# Ribatski_EPS-v2_0.net
KiCad netlist of a schematic drawn in EAGLE
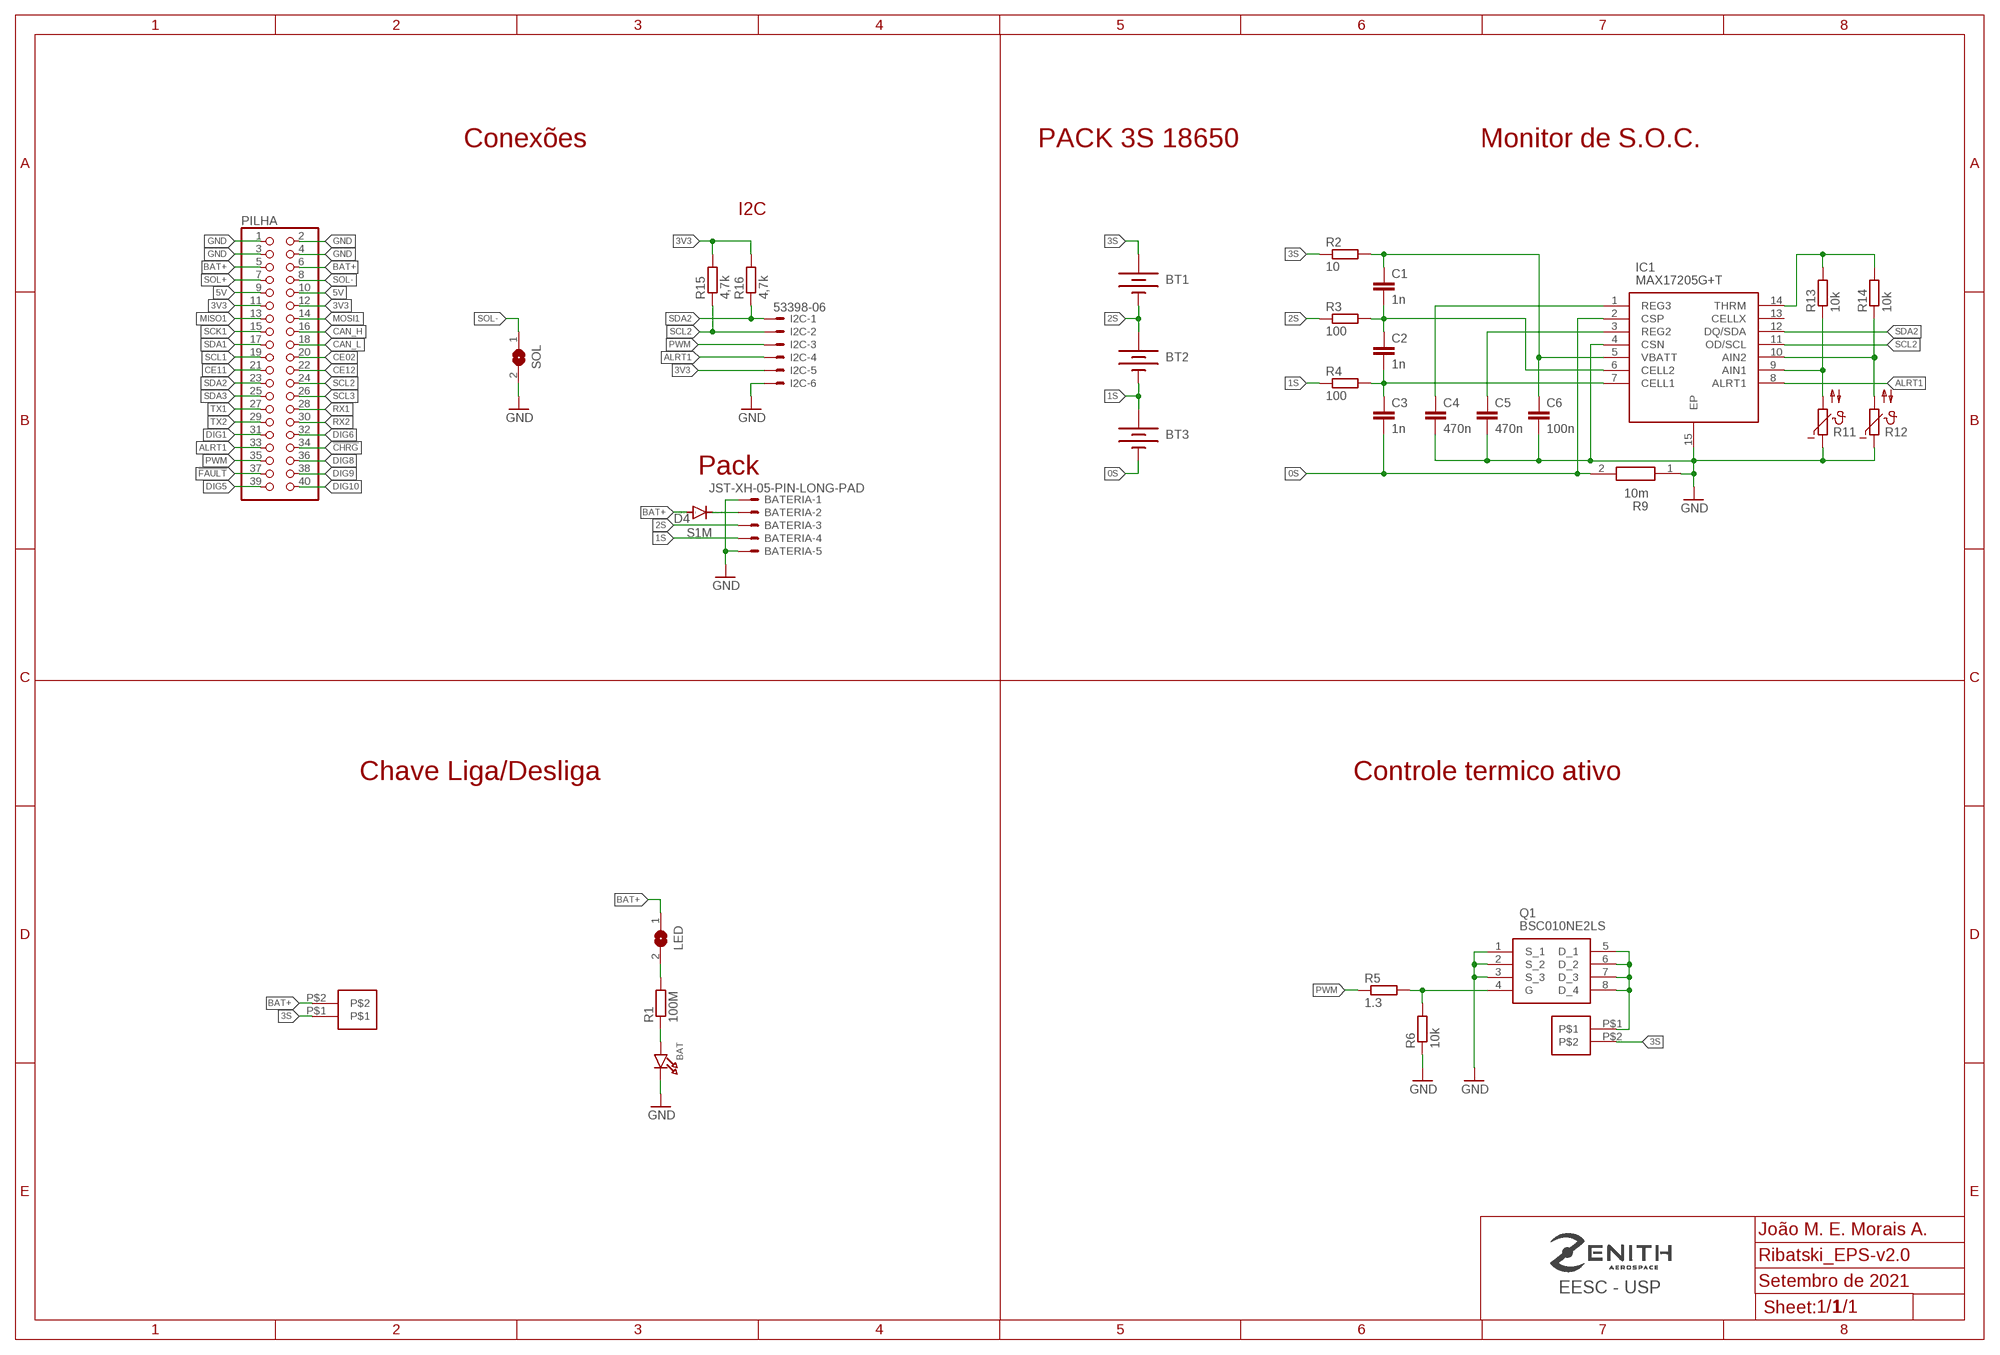
[diagram p0: schematic, sheet 1]

(export (version "E")
  (design (tool "Eeschema 10.0.6"))
  (components
    (comp (ref "BAT")
      (value "LED1206")
      (footprint "eagle-import:CHIPLED_1206")
      (libsource (lib "eagle-import") (part "LED1206"))
    )
    (comp (ref "BATERIA")
      (value "JST-XH-05-PIN-LONG-PAD")
      (footprint "eagle-import:JST-XH-05-PACKAGE-LONG-PAD")
      (libsource (lib "eagle-import") (part "JST-XH-05-PIN-LONG-PAD"))
    )
    (comp (ref "BT1")
      (value "BATTERY-18650")
      (footprint "eagle-import:BATTERY_18650-HOLDER")
      (libsource (lib "eagle-import") (part "BATTERY-18650"))
    )
    (comp (ref "BT2")
      (value "BATTERY-18650")
      (footprint "eagle-import:BATTERY_18650-HOLDER")
      (libsource (lib "eagle-import") (part "BATTERY-18650"))
    )
    (comp (ref "BT3")
      (value "BATTERY-18650")
      (footprint "eagle-import:BATTERY_18650-HOLDER")
      (libsource (lib "eagle-import") (part "BATTERY-18650"))
    )
    (comp (ref "C1")
      (value "1n")
      (footprint "eagle-import:C0805")
      (libsource (lib "eagle-import") (part "C-EUC0805"))
    )
    (comp (ref "C2")
      (value "1n")
      (footprint "eagle-import:C0805")
      (libsource (lib "eagle-import") (part "C-EUC0805"))
    )
    (comp (ref "C3")
      (value "1n")
      (footprint "eagle-import:C0805")
      (libsource (lib "eagle-import") (part "C-EUC0805"))
    )
    (comp (ref "C4")
      (value "470n")
      (footprint "eagle-import:C0805")
      (libsource (lib "eagle-import") (part "C-EUC0805"))
    )
    (comp (ref "C5")
      (value "470n")
      (footprint "eagle-import:C0805")
      (libsource (lib "eagle-import") (part "C-EUC0805"))
    )
    (comp (ref "C6")
      (value "100n")
      (footprint "eagle-import:C0805")
      (libsource (lib "eagle-import") (part "C-EUC0805"))
    )
    (comp (ref "D4")
      (value "S1M")
      (footprint "eagle-import:SMA")
      (libsource (lib "eagle-import") (part "S1M"))
    )
    (comp (ref "I2C")
      (value "53398-06")
      (footprint "eagle-import:53398-06")
      (fields (field (name "MF") "MOLEX"))
      (libsource (lib "eagle-import") (part "53?-06398"))
    )
    (comp (ref "IC1")
      (value "MAX17205G+T")
      (footprint "eagle-import:SON40P300X300X80-15N")
      (fields (field (name "MOUSER_PART_NUMBER") "700-MAX17205G+T"))
      (libsource (lib "eagle-import") (part "MAX17205G+T"))
    )
    (comp (ref "LED")
      (value "SOLDERJUMPERREFLOW_NOPASTE")
      (footprint "eagle-import:SOLDERJUMPER_REFLOW_NOPASTE")
      (libsource (lib "eagle-import") (part "SOLDERJUMPERREFLOW_NOPASTE"))
    )
    (comp (ref "PILHA")
      (value "PINHD-2X20")
      (footprint "eagle-import:2X20")
      (libsource (lib "eagle-import") (part "PINHD-2X20"))
    )
    (comp (ref "Q1")
      (value "BSC010NE2LS")
      (footprint "eagle-import:PG-TDSON-8")
      (fields (field (name "MOUSER_PART_NUMBER") "726-BSC010NE2LS"))
      (libsource (lib "eagle-import") (part "BSC010NE2LS"))
    )
    (comp (ref "R1")
      (value "100M")
      (footprint "eagle-import:R0805")
      (libsource (lib "eagle-import") (part "R-EU_R0805"))
    )
    (comp (ref "R2")
      (value "10")
      (footprint "eagle-import:0204_7")
      (libsource (lib "eagle-import") (part "R-EU_0204/7"))
    )
    (comp (ref "R3")
      (value "100")
      (footprint "eagle-import:0204_7")
      (libsource (lib "eagle-import") (part "R-EU_0204/7"))
    )
    (comp (ref "R4")
      (value "100")
      (footprint "eagle-import:0204_7")
      (libsource (lib "eagle-import") (part "R-EU_0204/7"))
    )
    (comp (ref "R5")
      (value "1.3")
      (footprint "eagle-import:R0805")
      (libsource (lib "eagle-import") (part "R-EU_R0805"))
    )
    (comp (ref "R6")
      (value "10k")
      (footprint "eagle-import:R0805")
      (libsource (lib "eagle-import") (part "R-EU_R0805"))
    )
    (comp (ref "R9")
      (value "10m")
      (footprint "eagle-import:GMR320HJBFA10L0")
      (fields
        (field (name "MANUFACTURER_PART_NUMBER") "GMR320HJBFA10L0")
        (field (name "MOUSER_PART_NUMBER") "755-GMR320HJBFA10L0")
      )
      (libsource (lib "eagle-import") (part "GMR320HJBFA10L0"))
    )
    (comp (ref "R11")
      (value "NTC640")
      (footprint "eagle-import:P640")
      (libsource (lib "eagle-import") (part "NTC640"))
    )
    (comp (ref "R12")
      (value "NTC640")
      (footprint "eagle-import:P640")
      (libsource (lib "eagle-import") (part "NTC640"))
    )
    (comp (ref "R13")
      (value "10k")
      (footprint "eagle-import:R0805")
      (libsource (lib "eagle-import") (part "R-EU_R0805"))
    )
    (comp (ref "R14")
      (value "10k")
      (footprint "eagle-import:R0805")
      (libsource (lib "eagle-import") (part "R-EU_R0805"))
    )
    (comp (ref "R15")
      (value "4,7k")
      (footprint "eagle-import:R0805")
      (libsource (lib "eagle-import") (part "R-EU_R0805"))
    )
    (comp (ref "R16")
      (value "4,7k")
      (footprint "eagle-import:R0805")
      (libsource (lib "eagle-import") (part "R-EU_R0805"))
    )
    (comp (ref "SOL")
      (value "SOLDERJUMPERREFLOW_NOPASTE")
      (footprint "eagle-import:SOLDERJUMPER_REFLOW_NOPASTE")
      (libsource (lib "eagle-import") (part "SOLDERJUMPERREFLOW_NOPASTE"))
    )
    (comp (ref "U$1")
      (value "S02B-XASS-1")
      (footprint "eagle-import:S02B-XASS-1")
      (libsource (lib "eagle-import") (part "S02B-XASS-1"))
    )
    (comp (ref "U$2")
      (value "B02B-XASK-1")
      (footprint "eagle-import:B02B-XASK-1")
      (libsource (lib "eagle-import") (part "B02B-XASK-1"))
    )
  )
  (nets
    (net (code "1") (name "/~{CHRG}") (class "Default")
      (node (ref "PILHA") (pin "34") (pinfunction "34_34") (pintype "passive"))
    )
    (net (code "2") (name "/~{FAULT}") (class "Default")
      (node (ref "PILHA") (pin "37") (pinfunction "37_37") (pintype "passive"))
    )
    (net (code "3") (name "0S") (class "Default")
      (node (ref "BT3") (pin "GND@1") (pinfunction "-_GND@1") (pintype "power_in"))
      (node (ref "C3") (pin "2") (pinfunction "2_2") (pintype "passive"))
      (node (ref "IC1") (pin "2") (pinfunction "CSP_2") (pintype "bidirectional"))
      (node (ref "R9") (pin "2") (pinfunction "2_2") (pintype "bidirectional"))
    )
    (net (code "4") (name "1S") (class "Default")
      (node (ref "BATERIA") (pin "4") (pinfunction "S_4") (pintype "passive"))
      (node (ref "BT2") (pin "GND@1") (pinfunction "-_GND@1") (pintype "power_in"))
      (node (ref "BT3") (pin "PWR@1") (pinfunction "+_PWR@1") (pintype "power_in"))
      (node (ref "R4") (pin "1") (pinfunction "1_1") (pintype "passive"))
    )
    (net (code "5") (name "2S") (class "Default")
      (node (ref "BATERIA") (pin "3") (pinfunction "S_3") (pintype "passive"))
      (node (ref "BT1") (pin "GND@1") (pinfunction "-_GND@1") (pintype "power_in"))
      (node (ref "BT2") (pin "PWR@1") (pinfunction "+_PWR@1") (pintype "power_in"))
      (node (ref "R3") (pin "1") (pinfunction "1_1") (pintype "passive"))
    )
    (net (code "6") (name "3S") (class "Default")
      (node (ref "BT1") (pin "PWR@1") (pinfunction "+_PWR@1") (pintype "power_in"))
      (node (ref "R2") (pin "1") (pinfunction "1_1") (pintype "passive"))
      (node (ref "U$1") (pin "P$1") (pinfunction "P$1_P$1") (pintype "bidirectional"))
      (node (ref "U$2") (pin "P$2") (pinfunction "P$2_P$2") (pintype "bidirectional"))
    )
    (net (code "7") (name "3V3") (class "Default")
      (node (ref "I2C") (pin "5") (pinfunction "S_5") (pintype "passive"))
      (node (ref "PILHA") (pin "11") (pinfunction "11_11") (pintype "passive"))
      (node (ref "PILHA") (pin "12") (pinfunction "12_12") (pintype "passive"))
      (node (ref "R15") (pin "2") (pinfunction "2_2") (pintype "passive"))
      (node (ref "R16") (pin "2") (pinfunction "2_2") (pintype "passive"))
    )
    (net (code "8") (name "5V") (class "Default")
      (node (ref "PILHA") (pin "10") (pinfunction "10_10") (pintype "passive"))
      (node (ref "PILHA") (pin "9") (pinfunction "9_9") (pintype "passive"))
    )
    (net (code "9") (name "ALRT1") (class "Default")
      (node (ref "I2C") (pin "4") (pinfunction "S_4") (pintype "passive"))
      (node (ref "IC1") (pin "8") (pinfunction "ALRT1_8") (pintype "bidirectional"))
      (node (ref "PILHA") (pin "33") (pinfunction "33_33") (pintype "passive"))
    )
    (net (code "10") (name "BAT+") (class "Default")
      (node (ref "D4") (pin "A") (pinfunction "A_A") (pintype "passive"))
      (node (ref "LED") (pin "1") (pinfunction "1_1") (pintype "passive"))
      (node (ref "PILHA") (pin "5") (pinfunction "5_5") (pintype "passive"))
      (node (ref "PILHA") (pin "6") (pinfunction "6_6") (pintype "passive"))
      (node (ref "U$1") (pin "P$2") (pinfunction "P$2_P$2") (pintype "bidirectional"))
    )
    (net (code "11") (name "CAN_H") (class "Default")
      (node (ref "PILHA") (pin "16") (pinfunction "16_16") (pintype "passive"))
    )
    (net (code "12") (name "CAN_L") (class "Default")
      (node (ref "PILHA") (pin "18") (pinfunction "18_18") (pintype "passive"))
    )
    (net (code "13") (name "CE02") (class "Default")
      (node (ref "PILHA") (pin "20") (pinfunction "20_20") (pintype "passive"))
    )
    (net (code "14") (name "CE11") (class "Default")
      (node (ref "PILHA") (pin "21") (pinfunction "21_21") (pintype "passive"))
    )
    (net (code "15") (name "CE12") (class "Default")
      (node (ref "PILHA") (pin "22") (pinfunction "22_22") (pintype "passive"))
    )
    (net (code "16") (name "DIG1") (class "Default")
      (node (ref "PILHA") (pin "31") (pinfunction "31_31") (pintype "passive"))
    )
    (net (code "17") (name "DIG5") (class "Default")
      (node (ref "PILHA") (pin "39") (pinfunction "39_39") (pintype "passive"))
    )
    (net (code "18") (name "DIG6") (class "Default")
      (node (ref "PILHA") (pin "32") (pinfunction "32_32") (pintype "passive"))
    )
    (net (code "19") (name "DIG8") (class "Default")
      (node (ref "PILHA") (pin "36") (pinfunction "36_36") (pintype "passive"))
    )
    (net (code "20") (name "DIG9") (class "Default")
      (node (ref "PILHA") (pin "38") (pinfunction "38_38") (pintype "passive"))
    )
    (net (code "21") (name "DIG10") (class "Default")
      (node (ref "PILHA") (pin "40") (pinfunction "40_40") (pintype "passive"))
    )
    (net (code "22") (name "GND") (class "Default")
      (node (ref "BAT") (pin "C") (pinfunction "C_C") (pintype "passive"))
      (node (ref "BATERIA") (pin "1") (pinfunction "S_1") (pintype "passive"))
      (node (ref "BATERIA") (pin "5") (pinfunction "S_5") (pintype "passive"))
      (node (ref "C4") (pin "2") (pinfunction "2_2") (pintype "passive"))
      (node (ref "C5") (pin "2") (pinfunction "2_2") (pintype "passive"))
      (node (ref "C6") (pin "2") (pinfunction "2_2") (pintype "passive"))
      (node (ref "I2C") (pin "6") (pinfunction "S_6") (pintype "passive"))
      (node (ref "IC1") (pin "15") (pinfunction "EP_15") (pintype "bidirectional"))
      (node (ref "IC1") (pin "4") (pinfunction "CSN_4") (pintype "bidirectional"))
      (node (ref "PILHA") (pin "1") (pinfunction "1_1") (pintype "passive"))
      (node (ref "PILHA") (pin "2") (pinfunction "2_2") (pintype "passive"))
      (node (ref "PILHA") (pin "3") (pinfunction "3_3") (pintype "passive"))
      (node (ref "PILHA") (pin "4") (pinfunction "4_4") (pintype "passive"))
      (node (ref "Q1") (pin "1") (pinfunction "S_1_1") (pintype "bidirectional"))
      (node (ref "Q1") (pin "2") (pinfunction "S_2_2") (pintype "bidirectional"))
      (node (ref "Q1") (pin "3") (pinfunction "S_3_3") (pintype "bidirectional"))
      (node (ref "R11") (pin "1") (pinfunction "1_1") (pintype "passive"))
      (node (ref "R12") (pin "1") (pinfunction "1_1") (pintype "passive"))
      (node (ref "R6") (pin "1") (pinfunction "1_1") (pintype "passive"))
      (node (ref "R9") (pin "1") (pinfunction "1_1") (pintype "bidirectional"))
      (node (ref "SOL") (pin "2") (pinfunction "2_2") (pintype "passive"))
    )
    (net (code "23") (name "MISO1") (class "Default")
      (node (ref "PILHA") (pin "13") (pinfunction "13_13") (pintype "passive"))
    )
    (net (code "24") (name "MOSI1") (class "Default")
      (node (ref "PILHA") (pin "14") (pinfunction "14_14") (pintype "passive"))
    )
    (net (code "25") (name "Net-(BAT-PadA)") (class "Default")
      (node (ref "BAT") (pin "A") (pinfunction "A_A") (pintype "passive"))
      (node (ref "R1") (pin "1") (pinfunction "1_1") (pintype "passive"))
    )
    (net (code "26") (name "Net-(BATERIAB-S)") (class "Default")
      (node (ref "BATERIA") (pin "2") (pinfunction "S_2") (pintype "passive"))
      (node (ref "D4") (pin "C") (pinfunction "C_C") (pintype "passive"))
    )
    (net (code "27") (name "Net-(IC1-AIN1)") (class "Default")
      (node (ref "IC1") (pin "9") (pinfunction "AIN1_9") (pintype "bidirectional"))
      (node (ref "R11") (pin "2") (pinfunction "2_2") (pintype "passive"))
      (node (ref "R13") (pin "1") (pinfunction "1_1") (pintype "passive"))
    )
    (net (code "28") (name "Net-(IC1-AIN2)") (class "Default")
      (node (ref "IC1") (pin "10") (pinfunction "AIN2_10") (pintype "bidirectional"))
      (node (ref "R12") (pin "2") (pinfunction "2_2") (pintype "passive"))
      (node (ref "R14") (pin "1") (pinfunction "1_1") (pintype "passive"))
    )
    (net (code "29") (name "Net-(IC1-CELL1)") (class "Default")
      (node (ref "C2") (pin "2") (pinfunction "2_2") (pintype "passive"))
      (node (ref "C3") (pin "1") (pinfunction "1_1") (pintype "passive"))
      (node (ref "IC1") (pin "7") (pinfunction "CELL1_7") (pintype "bidirectional"))
      (node (ref "R4") (pin "2") (pinfunction "2_2") (pintype "passive"))
    )
    (net (code "30") (name "Net-(IC1-CELL2)") (class "Default")
      (node (ref "C1") (pin "2") (pinfunction "2_2") (pintype "passive"))
      (node (ref "C2") (pin "1") (pinfunction "1_1") (pintype "passive"))
      (node (ref "IC1") (pin "6") (pinfunction "CELL2_6") (pintype "bidirectional"))
      (node (ref "R3") (pin "2") (pinfunction "2_2") (pintype "passive"))
    )
    (net (code "31") (name "Net-(IC1-REG2)") (class "Default")
      (node (ref "C5") (pin "1") (pinfunction "1_1") (pintype "passive"))
      (node (ref "IC1") (pin "3") (pinfunction "REG2_3") (pintype "bidirectional"))
    )
    (net (code "32") (name "Net-(IC1-REG3)") (class "Default")
      (node (ref "C4") (pin "1") (pinfunction "1_1") (pintype "passive"))
      (node (ref "IC1") (pin "1") (pinfunction "REG3_1") (pintype "bidirectional"))
    )
    (net (code "33") (name "Net-(IC1-THRM)") (class "Default")
      (node (ref "IC1") (pin "14") (pinfunction "THRM_14") (pintype "bidirectional"))
      (node (ref "R13") (pin "2") (pinfunction "2_2") (pintype "passive"))
      (node (ref "R14") (pin "2") (pinfunction "2_2") (pintype "passive"))
    )
    (net (code "34") (name "Net-(IC1-VBATT)") (class "Default")
      (node (ref "C1") (pin "1") (pinfunction "1_1") (pintype "passive"))
      (node (ref "C6") (pin "1") (pinfunction "1_1") (pintype "passive"))
      (node (ref "IC1") (pin "5") (pinfunction "VBATT_5") (pintype "bidirectional"))
      (node (ref "R2") (pin "2") (pinfunction "2_2") (pintype "passive"))
    )
    (net (code "35") (name "Net-(LED-Pad2)") (class "Default")
      (node (ref "LED") (pin "2") (pinfunction "2_2") (pintype "passive"))
      (node (ref "R1") (pin "2") (pinfunction "2_2") (pintype "passive"))
    )
    (net (code "36") (name "Net-(Q1-D_1)") (class "Default")
      (node (ref "Q1") (pin "5") (pinfunction "D_1_5") (pintype "bidirectional"))
      (node (ref "Q1") (pin "6") (pinfunction "D_2_6") (pintype "bidirectional"))
      (node (ref "Q1") (pin "7") (pinfunction "D_3_7") (pintype "bidirectional"))
      (node (ref "Q1") (pin "8") (pinfunction "D_4_8") (pintype "bidirectional"))
      (node (ref "U$2") (pin "P$1") (pinfunction "P$1_P$1") (pintype "bidirectional"))
    )
    (net (code "37") (name "Net-(Q1-G)") (class "Default")
      (node (ref "Q1") (pin "4") (pinfunction "G_4") (pintype "bidirectional"))
      (node (ref "R5") (pin "2") (pinfunction "2_2") (pintype "passive"))
      (node (ref "R6") (pin "2") (pinfunction "2_2") (pintype "passive"))
    )
    (net (code "38") (name "PWM") (class "Default")
      (node (ref "I2C") (pin "3") (pinfunction "S_3") (pintype "passive"))
      (node (ref "PILHA") (pin "35") (pinfunction "35_35") (pintype "passive"))
      (node (ref "R5") (pin "1") (pinfunction "1_1") (pintype "passive"))
    )
    (net (code "39") (name "RX1") (class "Default")
      (node (ref "PILHA") (pin "28") (pinfunction "28_28") (pintype "passive"))
    )
    (net (code "40") (name "RX2") (class "Default")
      (node (ref "PILHA") (pin "30") (pinfunction "30_30") (pintype "passive"))
    )
    (net (code "41") (name "SCK1") (class "Default")
      (node (ref "PILHA") (pin "15") (pinfunction "15_15") (pintype "passive"))
    )
    (net (code "42") (name "SCL1") (class "Default")
      (node (ref "PILHA") (pin "19") (pinfunction "19_19") (pintype "passive"))
    )
    (net (code "43") (name "SCL2") (class "Default")
      (node (ref "I2C") (pin "2") (pinfunction "S_2") (pintype "passive"))
      (node (ref "IC1") (pin "11") (pinfunction "OD/SCL_11") (pintype "bidirectional"))
      (node (ref "PILHA") (pin "24") (pinfunction "24_24") (pintype "passive"))
      (node (ref "R15") (pin "1") (pinfunction "1_1") (pintype "passive"))
    )
    (net (code "44") (name "SCL3") (class "Default")
      (node (ref "PILHA") (pin "26") (pinfunction "26_26") (pintype "passive"))
    )
    (net (code "45") (name "SDA1") (class "Default")
      (node (ref "PILHA") (pin "17") (pinfunction "17_17") (pintype "passive"))
    )
    (net (code "46") (name "SDA2") (class "Default")
      (node (ref "I2C") (pin "1") (pinfunction "S_1") (pintype "passive"))
      (node (ref "IC1") (pin "12") (pinfunction "DQ/SDA_12") (pintype "bidirectional"))
      (node (ref "PILHA") (pin "23") (pinfunction "23_23") (pintype "passive"))
      (node (ref "R16") (pin "1") (pinfunction "1_1") (pintype "passive"))
    )
    (net (code "47") (name "SDA3") (class "Default")
      (node (ref "PILHA") (pin "25") (pinfunction "25_25") (pintype "passive"))
    )
    (net (code "48") (name "SOL+") (class "Default")
      (node (ref "PILHA") (pin "7") (pinfunction "7_7") (pintype "passive"))
    )
    (net (code "49") (name "SOL-") (class "Default")
      (node (ref "PILHA") (pin "8") (pinfunction "8_8") (pintype "passive"))
      (node (ref "SOL") (pin "1") (pinfunction "1_1") (pintype "passive"))
    )
    (net (code "50") (name "TX1") (class "Default")
      (node (ref "PILHA") (pin "27") (pinfunction "27_27") (pintype "passive"))
    )
    (net (code "51") (name "TX2") (class "Default")
      (node (ref "PILHA") (pin "29") (pinfunction "29_29") (pintype "passive"))
    )
    (net (code "52") (name "unconnected-(IC1-CELLX-Pad13)") (class "Default")
      (node (ref "IC1") (pin "13") (pinfunction "CELLX_13") (pintype "bidirectional"))
    )
  )
)
